# power.net
KiCad netlist of a schematic drawn in Altium Designer
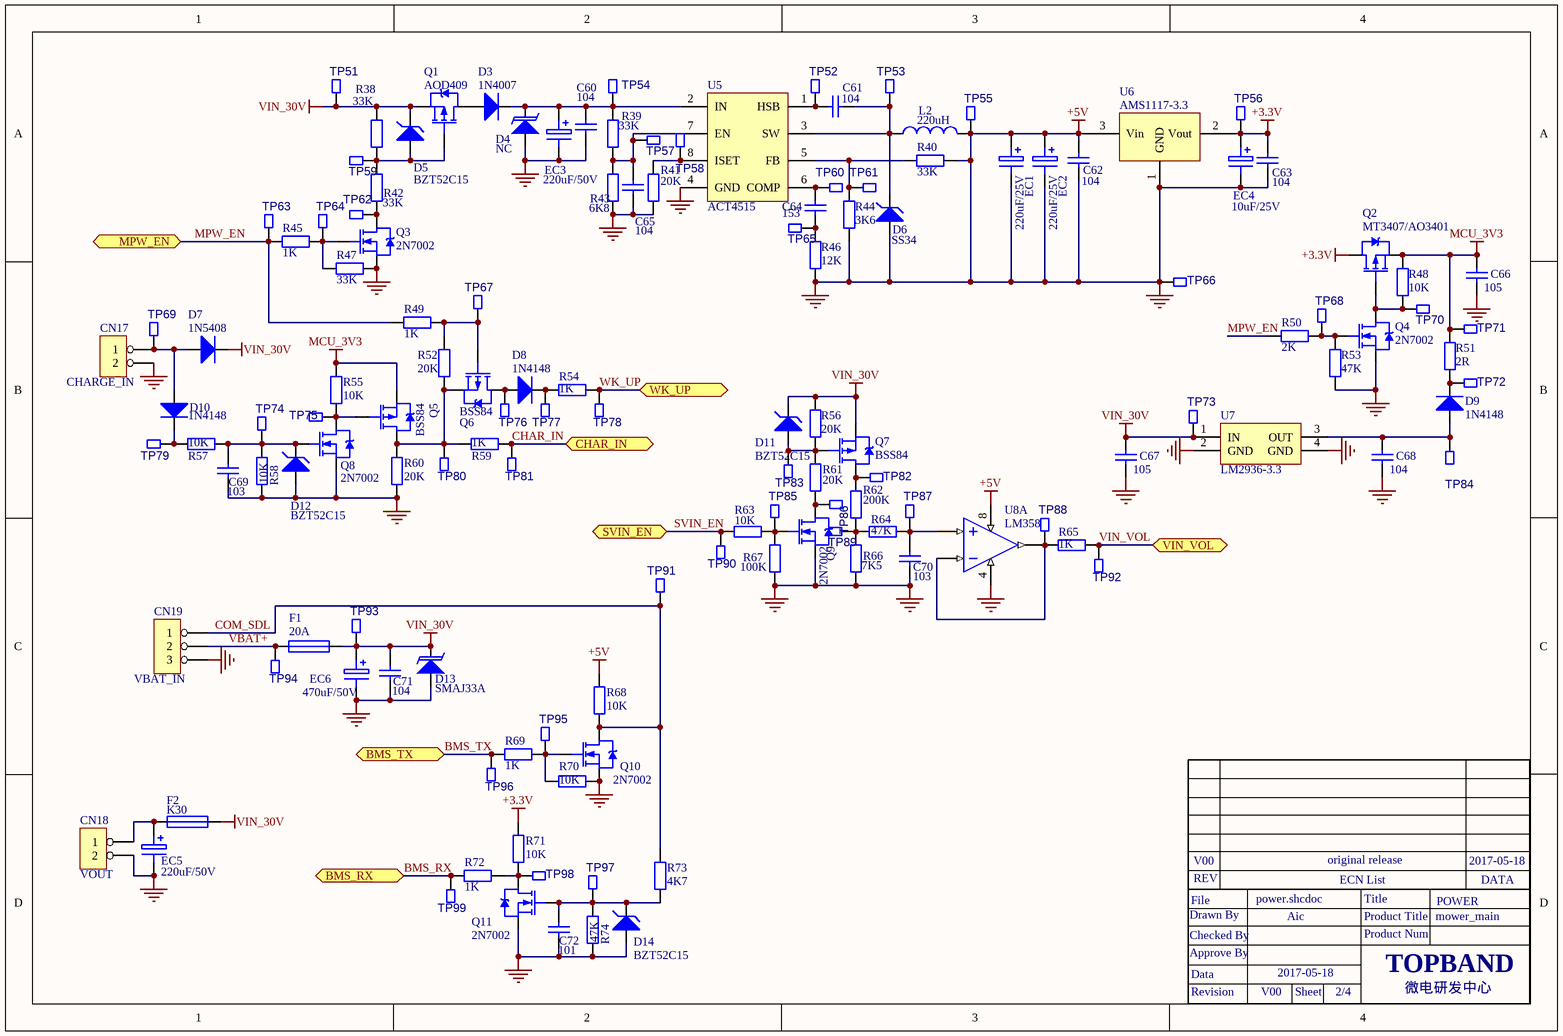
[diagram p0: power.SchDoc]

(export (version "E")
  (design (tool "Eeschema 10.0.6"))
  (components
    (comp (ref "C60")
      (value "104")
      (footprint "0603C")
      (libsource (lib "altium-import") (part "root_1_mirrored_Cap(0603)_"))
    )
    (comp (ref "C61")
      (value "104")
      (footprint "0603C")
      (libsource (lib "altium-import") (part "root_2_mirrored_Cap(0603)_"))
    )
    (comp (ref "C62")
      (value "104")
      (footprint "0603C")
      (libsource (lib "altium-import") (part "root_1_mirrored_Cap(0603)_"))
    )
    (comp (ref "C63")
      (value "104")
      (footprint "0603C")
      (libsource (lib "altium-import") (part "root_1_mirrored_Cap(0603)_"))
    )
    (comp (ref "C64")
      (value "153")
      (footprint "0603C")
      (libsource (lib "altium-import") (part "root_1_mirrored_Cap(0603)_"))
    )
    (comp (ref "C65")
      (value "104")
      (footprint "0603C")
      (libsource (lib "altium-import") (part "root_1_mirrored_Cap(0603)_"))
    )
    (comp (ref "C66")
      (value "105")
      (footprint "0603C")
      (libsource (lib "altium-import") (part "root_1_mirrored_Cap(0603)_"))
    )
    (comp (ref "C67")
      (value "105")
      (footprint "0603C")
      (libsource (lib "altium-import") (part "root_1_mirrored_Cap(0603)_"))
    )
    (comp (ref "C68")
      (value "104")
      (footprint "0603C")
      (libsource (lib "altium-import") (part "root_1_mirrored_Cap(0603)_"))
    )
    (comp (ref "C69")
      (value "103")
      (footprint "0603C")
      (libsource (lib "altium-import") (part "root_3_mirrored_Cap(0603)_"))
    )
    (comp (ref "C70")
      (value "103")
      (footprint "0603C")
      (description "电容器")
      (fields (field (name "PART NUMBER") "Cap(0603)"))
      (libsource (lib "分立器件1") (part "Cap(0603)"))
    )
    (comp (ref "C71")
      (value "104")
      (footprint "0805C")
      (libsource (lib "altium-import") (part "root_3_mirrored_Cap(0603)_"))
    )
    (comp (ref "C72")
      (value "101")
      (footprint "0603C")
      (libsource (lib "altium-import") (part "root_3_mirrored_Cap(0603)_"))
    )
    (comp (ref "CN17")
      (value "CHARGE_IN")
      (footprint "CON2-2.54")
      (description "插座")
      (fields (field (name "PART NUMBER") "2Pin(卧式)"))
      (libsource (lib "接插器件+IC") (part "2Pin(卧式)"))
    )
    (comp (ref "CN18")
      (value "VOUT")
      (footprint "CON2-3.96")
      (description "插座")
      (fields (field (name "PART NUMBER") "2Pin(卧式)"))
      (libsource (lib "接插器件+IC") (part "2Pin(卧式)"))
    )
    (comp (ref "CN19")
      (value "VBAT_IN")
      (footprint "CON3-3.96")
      (description "插座")
      (fields (field (name "PART NUMBER") "3Pin(2~3.96mm)"))
      (libsource (lib "接插器件+IC") (part "3Pin(2~3.96mm)"))
    )
    (comp (ref "D3")
      (value "1N4007")
      (footprint "SMA")
      (description "二极管")
      (fields (field (name "PART NUMBER") "Diode(DO-35)-D"))
      (libsource (lib "分立器件1") (part "Diode(DO-35)-D"))
    )
    (comp (ref "D4")
      (value "NC")
      (footprint "SOD-123")
      (description "TVS管")
      (fields (field (name "PART NUMBER") "Diode(TVS_贴片)_1"))
      (libsource (lib "分立器件1") (part "Diode(TVS_贴片)_1"))
    )
    (comp (ref "D5")
      (value "BZT52C15")
      (footprint "SOD-123")
      (description "稳压二极管")
      (fields (field (name "PART NUMBER") "D Zener(贴片)"))
      (libsource (lib "分立器件1") (part "D Zener(贴片)"))
    )
    (comp (ref "D6")
      (value "SS34")
      (footprint "SMA")
      (description "稳压二极管")
      (fields (field (name "PART NUMBER") "D Zener(贴片)"))
      (libsource (lib "分立器件1") (part "D Zener(贴片)"))
    )
    (comp (ref "D7")
      (value "1N5408")
      (footprint "DIODE")
      (description "二极管")
      (fields (field (name "PART NUMBER") "Diode(DO-35)-D"))
      (libsource (lib "分立器件1") (part "Diode(DO-35)-D"))
    )
    (comp (ref "D8")
      (value "1N4148")
      (footprint "SOD-123")
      (description "二极管")
      (fields (field (name "PART NUMBER") "Diode(DO-35)-D"))
      (libsource (lib "分立器件1") (part "Diode(DO-35)-D"))
    )
    (comp (ref "D9")
      (value "1N4148")
      (footprint "SOD-123")
      (description "二极管")
      (fields (field (name "PART NUMBER") "Diode(DO-35)-D"))
      (libsource (lib "分立器件1") (part "Diode(DO-35)-D"))
    )
    (comp (ref "D10")
      (value "1N4148")
      (footprint "SOD-123")
      (description "二极管")
      (fields (field (name "PART NUMBER") "Diode(DO-35)-D"))
      (libsource (lib "分立器件1") (part "Diode(DO-35)-D"))
    )
    (comp (ref "D11")
      (value "BZT52C15")
      (footprint "SOD-123")
      (description "稳压二极管")
      (fields (field (name "PART NUMBER") "D Zener(贴片)"))
      (libsource (lib "分立器件1") (part "D Zener(贴片)"))
    )
    (comp (ref "D12")
      (value "BZT52C15")
      (footprint "SOD-123")
      (description "稳压二极管")
      (fields (field (name "PART NUMBER") "D Zener(贴片)"))
      (libsource (lib "分立器件1") (part "D Zener(贴片)"))
    )
    (comp (ref "D13")
      (value "SMAJ33A")
      (footprint "DO-214AC")
      (description "TVS管")
      (fields (field (name "PART NUMBER") "Diode(TVS_贴片)_1"))
      (libsource (lib "分立器件1") (part "Diode(TVS_贴片)_1"))
    )
    (comp (ref "D14")
      (value "BZT52C15")
      (footprint "SOD-123")
      (description "稳压二极管")
      (fields (field (name "PART NUMBER") "D Zener(贴片)"))
      (libsource (lib "分立器件1") (part "D Zener(贴片)"))
    )
    (comp (ref "EC1")
      (value "220uF/25V")
      (footprint "EC10")
      (description "电解电容")
      (fields (field (name "PART NUMBER") "Electro(2.5mm)"))
      (libsource (lib "分立器件1") (part "Electro(2.5mm)"))
    )
    (comp (ref "EC2")
      (value "220uF/25V")
      (footprint "EC10")
      (description "电解电容")
      (fields (field (name "PART NUMBER") "Electro(2.5mm)"))
      (libsource (lib "分立器件1") (part "Electro(2.5mm)"))
    )
    (comp (ref "EC3")
      (value "220uF/50V")
      (footprint "EC10")
      (description "电解电容")
      (fields (field (name "PART NUMBER") "Electro(2.5mm)"))
      (libsource (lib "分立器件1") (part "Electro(2.5mm)"))
    )
    (comp (ref "EC4")
      (value "10uF/25V")
      (footprint "EC4")
      (description "电解电容")
      (fields (field (name "PART NUMBER") "Electro(2.5mm)"))
      (libsource (lib "分立器件1") (part "Electro(2.5mm)"))
    )
    (comp (ref "EC5")
      (value "220uF/50V")
      (footprint "EC10")
      (description "电解电容")
      (fields (field (name "PART NUMBER") "Electro(2.5mm)"))
      (libsource (lib "分立器件1") (part "Electro(2.5mm)"))
    )
    (comp (ref "EC6")
      (value "470uF/50V")
      (footprint "EC12.5")
      (description "电解电容")
      (fields (field (name "PART NUMBER") "Electro(2.5mm)"))
      (libsource (lib "分立器件1") (part "Electro(2.5mm)"))
    )
    (comp (ref "F1")
      (value "20A")
      (description "保险管")
      (fields (field (name "PART NUMBER") "Fuse(1206)"))
      (libsource (lib "分立器件1") (part "Fuse(1206)"))
    )
    (comp (ref "F2")
      (value "K30")
      (description "保险管")
      (fields (field (name "PART NUMBER") "Fuse(1206)"))
      (libsource (lib "分立器件1") (part "Fuse(1206)"))
    )
    (comp (ref "L2")
      (value "220uH")
      (footprint "150700618")
      (description "电感")
      (fields (field (name "PART NUMBER") "Inductor(0805)"))
      (libsource (lib "分立器件1") (part "Inductor(0805)"))
    )
    (comp (ref "Q1")
      (value "AOD409")
      (footprint "D-PACK-GDS")
      (description "MOS管")
      (fields (field (name "PART NUMBER") "PMOS-2"))
      (libsource (lib "分立器件1") (part "PMOS-2"))
    )
    (comp (ref "Q2")
      (value "MT3407/AO3401")
      (footprint "SOT23-GDS")
      (description "MOS管")
      (fields (field (name "PART NUMBER") "PMOS-2"))
      (libsource (lib "") (part "PMOS-2_1"))
    )
    (comp (ref "Q3")
      (value "2N7002")
      (footprint "SOT23-GDS")
      (description "MOS管")
      (fields (field (name "PART NUMBER") "NMOS-2"))
      (libsource (lib "分立器件1") (part "NMOS-2"))
    )
    (comp (ref "Q4")
      (value "2N7002")
      (footprint "SOD23-GDS")
      (description "MOS管")
      (fields (field (name "PART NUMBER") "NMOS-2"))
      (libsource (lib "分立器件1") (part "NMOS-2"))
    )
    (comp (ref "Q5")
      (value "BSS84")
      (footprint "SOT-23-GDS")
      (description "MOS管")
      (fields (field (name "PART NUMBER") "PMOS-2"))
      (libsource (lib "") (part "PMOS-2_1"))
    )
    (comp (ref "Q6")
      (value "BSS84")
      (footprint "SOT-23-GDS")
      (description "MOS管")
      (fields (field (name "PART NUMBER") "PMOS-2"))
      (libsource (lib "分立器件1") (part "PMOS-2"))
    )
    (comp (ref "Q7")
      (value "BSS84")
      (footprint "SOT-23-GDS")
      (description "MOS管")
      (fields (field (name "PART NUMBER") "PMOS-2"))
      (libsource (lib "") (part "PMOS-2_1"))
    )
    (comp (ref "Q8")
      (value "2N7002")
      (footprint "SOT-23-GDS")
      (description "MOS管")
      (fields (field (name "PART NUMBER") "NMOS-2"))
      (libsource (lib "分立器件1") (part "NMOS-2"))
    )
    (comp (ref "Q9")
      (value "2N7002")
      (footprint "SOT-23-GDS")
      (description "MOS管")
      (fields (field (name "PART NUMBER") "NMOS-2"))
      (libsource (lib "分立器件1") (part "NMOS-2"))
    )
    (comp (ref "Q10")
      (value "2N7002")
      (footprint "SOT-23-GDS")
      (description "MOS管")
      (fields (field (name "PART NUMBER") "NMOS-2"))
      (libsource (lib "分立器件1") (part "NMOS-2"))
    )
    (comp (ref "Q11")
      (value "2N7002")
      (footprint "SOT-23-GDS")
      (description "MOS管")
      (fields (field (name "PART NUMBER") "NMOS-2"))
      (libsource (lib "分立器件1") (part "NMOS-2"))
    )
    (comp (ref "R38")
      (value "33K")
      (footprint "0603R")
      (description "Resistor")
      (fields (field (name "PUBLISHER") "Altium Limited"))
      (libsource (lib "") (part "Res2_1"))
    )
    (comp (ref "R39")
      (value "33K")
      (footprint "0603R")
      (description "Resistor")
      (fields (field (name "PUBLISHER") "Altium Limited"))
      (libsource (lib "Miscellaneous Devices") (part "Res2"))
    )
    (comp (ref "R40")
      (value "33K")
      (footprint "0603R")
      (description "Resistor")
      (fields (field (name "PUBLISHER") "Altium Limited"))
      (libsource (lib "") (part "Res2_2"))
    )
    (comp (ref "R41")
      (value "20K")
      (footprint "0603R")
      (description "Resistor")
      (fields (field (name "PUBLISHER") "Altium Limited"))
      (libsource (lib "Miscellaneous Devices") (part "Res2"))
    )
    (comp (ref "R42")
      (value "33K")
      (footprint "0603R")
      (description "Resistor")
      (fields (field (name "PUBLISHER") "Altium Limited"))
      (libsource (lib "Miscellaneous Devices") (part "Res2"))
    )
    (comp (ref "R43")
      (value "6K8")
      (footprint "0603R")
      (description "Resistor")
      (fields (field (name "PUBLISHER") "Altium Limited"))
      (libsource (lib "Miscellaneous Devices") (part "Res2"))
    )
    (comp (ref "R44")
      (value "3K6")
      (footprint "0603R")
      (description "Resistor")
      (fields (field (name "PUBLISHER") "Altium Limited"))
      (libsource (lib "") (part "Res2_1"))
    )
    (comp (ref "R45")
      (value "1K")
      (footprint "0603R")
      (description "Resistor")
      (fields (field (name "PUBLISHER") "Altium Limited"))
      (libsource (lib "") (part "Res2_3"))
    )
    (comp (ref "R46")
      (value "12K")
      (footprint "0603R")
      (description "Resistor")
      (fields (field (name "PUBLISHER") "Altium Limited"))
      (libsource (lib "") (part "Res2_1"))
    )
    (comp (ref "R47")
      (value "33K")
      (footprint "0603R")
      (description "Resistor")
      (fields (field (name "PUBLISHER") "Altium Limited"))
      (libsource (lib "") (part "Res2_3"))
    )
    (comp (ref "R48")
      (value "10K")
      (footprint "0603R")
      (description "Resistor")
      (fields (field (name "PUBLISHER") "Altium Limited"))
      (libsource (lib "") (part "Res2_1"))
    )
    (comp (ref "R49")
      (value "1K")
      (footprint "0603R")
      (description "电阻器")
      (fields (field (name "PART NUMBER") "Res(0603)"))
      (libsource (lib "") (part "Res(0603)_1"))
    )
    (comp (ref "R50")
      (value "2K")
      (footprint "0603R")
      (description "Resistor")
      (fields (field (name "PUBLISHER") "Altium Limited"))
      (libsource (lib "") (part "Res2_2"))
    )
    (comp (ref "R51")
      (value "2R")
      (footprint "1206R")
      (description "Resistor")
      (fields (field (name "PUBLISHER") "Altium Limited"))
      (libsource (lib "") (part "Res2_1"))
    )
    (comp (ref "R52")
      (value "20K")
      (footprint "0603R")
      (description "电阻器")
      (fields (field (name "PART NUMBER") "Res(0603)"))
      (libsource (lib "") (part "Res(0603)_3"))
    )
    (comp (ref "R53")
      (value "47K")
      (footprint "0603R")
      (description "Resistor")
      (fields (field (name "PUBLISHER") "Altium Limited"))
      (libsource (lib "") (part "Res2_1"))
    )
    (comp (ref "R54")
      (value "1K")
      (footprint "0603R")
      (description "电阻器")
      (fields (field (name "PART NUMBER") "Res(0603)"))
      (libsource (lib "") (part "Res(0603)_1"))
    )
    (comp (ref "R55")
      (value "10K")
      (footprint "0603R")
      (description "电阻器")
      (fields (field (name "PART NUMBER") "Res(0603)"))
      (libsource (lib "分立器件1") (part "Res(0603)"))
    )
    (comp (ref "R56")
      (value "20K")
      (footprint "0603R")
      (description "电阻器")
      (fields (field (name "PART NUMBER") "Res(1206)"))
      (libsource (lib "分立器件1") (part "Res(1206)"))
    )
    (comp (ref "R57")
      (value "10K")
      (footprint "0603R")
      (description "电阻器")
      (fields (field (name "PART NUMBER") "Res(0603)"))
      (libsource (lib "") (part "Res(0603)_2"))
    )
    (comp (ref "R58")
      (value "10K")
      (footprint "0603R")
      (description "电阻器")
      (fields (field (name "PART NUMBER") "Res(0603)"))
      (libsource (lib "分立器件1") (part "Res(0603)"))
    )
    (comp (ref "R59")
      (value "1K")
      (footprint "0603R")
      (description "电阻器")
      (fields (field (name "PART NUMBER") "Res(0603)"))
      (libsource (lib "") (part "Res(0603)_1"))
    )
    (comp (ref "R60")
      (value "20K")
      (footprint "0603R")
      (description "电阻器")
      (fields (field (name "PART NUMBER") "Res(0603)"))
      (libsource (lib "分立器件1") (part "Res(0603)"))
    )
    (comp (ref "R61")
      (value "20K")
      (footprint "0603R")
      (description "电阻器")
      (fields (field (name "PART NUMBER") "Res(0603)"))
      (libsource (lib "") (part "Res(0603)_3"))
    )
    (comp (ref "R62")
      (value "200K")
      (footprint "0603R")
      (description "电阻器")
      (fields (field (name "PART NUMBER") "Res(0603)"))
      (libsource (lib "分立器件1") (part "Res(0603)"))
    )
    (comp (ref "R63")
      (value "10K")
      (footprint "0603R")
      (description "电阻器")
      (fields (field (name "PART NUMBER") "Res(0603)"))
      (libsource (lib "") (part "Res(0603)_2"))
    )
    (comp (ref "R64")
      (value "47K")
      (footprint "0603R")
      (description "电阻器")
      (fields (field (name "PART NUMBER") "Res(0603)"))
      (libsource (lib "") (part "Res(0603)_2"))
    )
    (comp (ref "R65")
      (value "1K")
      (footprint "0603R")
      (description "电阻器")
      (fields (field (name "PART NUMBER") "Res(0603)"))
      (libsource (lib "") (part "Res(0603)_1"))
    )
    (comp (ref "R66")
      (value "7K5")
      (footprint "0603R")
      (description "电阻器")
      (fields (field (name "PART NUMBER") "Res(0603)"))
      (libsource (lib "分立器件1") (part "Res(0603)"))
    )
    (comp (ref "R67")
      (value "100K")
      (footprint "0603R")
      (description "电阻器")
      (fields (field (name "PART NUMBER") "Res(0603)"))
      (libsource (lib "分立器件1") (part "Res(0603)"))
    )
    (comp (ref "R68")
      (value "10K")
      (footprint "0603R")
      (description "电阻器")
      (fields (field (name "PART NUMBER") "Res(0603)"))
      (libsource (lib "分立器件1") (part "Res(0603)"))
    )
    (comp (ref "R69")
      (value "1K")
      (footprint "0603R")
      (description "电阻器")
      (fields (field (name "PART NUMBER") "Res(0603)"))
      (libsource (lib "") (part "Res(0603)_1"))
    )
    (comp (ref "R70")
      (value "10K")
      (footprint "0603R")
      (description "电阻器")
      (fields (field (name "PART NUMBER") "Res(0603)"))
      (libsource (lib "") (part "Res(0603)_2"))
    )
    (comp (ref "R71")
      (value "10K")
      (footprint "0603R")
      (description "电阻器")
      (fields (field (name "PART NUMBER") "Res(0603)"))
      (libsource (lib "分立器件1") (part "Res(0603)"))
    )
    (comp (ref "R72")
      (value "1K")
      (footprint "0603R")
      (description "电阻器")
      (fields (field (name "PART NUMBER") "Res(0603)"))
      (libsource (lib "") (part "Res(0603)_1"))
    )
    (comp (ref "R73")
      (value "4K7")
      (footprint "0603R")
      (description "电阻器")
      (fields (field (name "PART NUMBER") "Res(0603)"))
      (libsource (lib "分立器件1") (part "Res(0603)"))
    )
    (comp (ref "R74")
      (value "47K")
      (footprint "0603R")
      (description "电阻器")
      (fields (field (name "PART NUMBER") "Res(0603)"))
      (libsource (lib "分立器件1") (part "Res(0603)"))
    )
    (comp (ref "TP51") (value "TP") (footprint "TEST-0.8MM") (libsource (lib "Topband1") (part "TP")))
    (comp (ref "TP52") (value "TP") (footprint "TEST-0.8MM") (libsource (lib "Topband1") (part "TP")))
    (comp (ref "TP53") (value "TP") (footprint "TEST-0.8MM") (libsource (lib "Topband1") (part "TP")))
    (comp (ref "TP54") (value "TP") (footprint "TEST-0.8MM") (libsource (lib "Topband1") (part "TP")))
    (comp (ref "TP55") (value "TP") (footprint "TEST-0.8MM") (libsource (lib "Topband1") (part "TP")))
    (comp (ref "TP56") (value "TP") (footprint "TEST-0.8MM") (libsource (lib "Topband1") (part "TP")))
    (comp (ref "TP57") (value "TP") (footprint "TEST-0.8MM") (libsource (lib "Topband1") (part "TP")))
    (comp (ref "TP58") (value "TP") (footprint "TEST-0.8MM") (libsource (lib "Topband1") (part "TP")))
    (comp (ref "TP59") (value "TP") (footprint "TEST-0.8MM") (libsource (lib "Topband1") (part "TP")))
    (comp (ref "TP60") (value "TP") (footprint "TEST-0.8MM") (libsource (lib "Topband1") (part "TP")))
    (comp (ref "TP61") (value "TP") (footprint "TEST-0.8MM") (libsource (lib "Topband1") (part "TP")))
    (comp (ref "TP62") (value "TP") (footprint "TEST-0.8MM") (libsource (lib "Topband1") (part "TP")))
    (comp (ref "TP63") (value "TP") (footprint "TEST-0.8MM") (libsource (lib "Topband1") (part "TP")))
    (comp (ref "TP64") (value "TP") (footprint "TEST-0.8MM") (libsource (lib "Topband1") (part "TP")))
    (comp (ref "TP65") (value "TP") (footprint "TEST-0.8MM") (libsource (lib "Topband1") (part "TP")))
    (comp (ref "TP66") (value "TP") (footprint "TEST-0.8MM") (libsource (lib "Topband1") (part "TP")))
    (comp (ref "TP67") (value "TP") (footprint "TEST-0.8MM") (libsource (lib "Topband1") (part "TP")))
    (comp (ref "TP68") (value "TP") (footprint "TEST-0.8MM") (libsource (lib "Topband1") (part "TP")))
    (comp (ref "TP69") (value "TP") (footprint "TEST-0.8MM") (libsource (lib "Topband1") (part "TP")))
    (comp (ref "TP70") (value "TP") (footprint "TEST-0.8MM") (libsource (lib "Topband1") (part "TP")))
    (comp (ref "TP71") (value "TP") (footprint "TEST-0.8MM") (libsource (lib "Topband1") (part "TP")))
    (comp (ref "TP72") (value "TP") (footprint "TEST-0.8MM") (libsource (lib "Topband1") (part "TP")))
    (comp (ref "TP73") (value "TP") (footprint "TEST-0.8MM") (libsource (lib "Topband1") (part "TP")))
    (comp (ref "TP74") (value "TP") (footprint "TEST-0.8MM") (libsource (lib "Topband1") (part "TP")))
    (comp (ref "TP75") (value "TP") (footprint "TEST-0.8MM") (libsource (lib "Topband1") (part "TP")))
    (comp (ref "TP76") (value "TP") (footprint "TEST-0.8MM") (libsource (lib "Topband1") (part "TP")))
    (comp (ref "TP77") (value "TP") (footprint "TEST-0.8MM") (libsource (lib "Topband1") (part "TP")))
    (comp (ref "TP78") (value "TP") (footprint "TEST-0.8MM") (libsource (lib "Topband1") (part "TP")))
    (comp (ref "TP79") (value "TP") (footprint "TEST-0.8MM") (libsource (lib "Topband1") (part "TP")))
    (comp (ref "TP80") (value "TP") (footprint "TEST-0.8MM") (libsource (lib "Topband1") (part "TP")))
    (comp (ref "TP81") (value "TP") (footprint "TEST-0.8MM") (libsource (lib "Topband1") (part "TP")))
    (comp (ref "TP82") (value "TP") (footprint "TEST-0.8MM") (libsource (lib "Topband1") (part "TP")))
    (comp (ref "TP83") (value "TP") (footprint "TEST-0.8MM") (libsource (lib "Topband1") (part "TP")))
    (comp (ref "TP84") (value "TP") (footprint "TEST-0.8MM") (libsource (lib "Topband1") (part "TP")))
    (comp (ref "TP85") (value "TP") (footprint "TEST-0.8MM") (libsource (lib "Topband1") (part "TP")))
    (comp (ref "TP86") (value "TP") (footprint "TEST-0.8MM") (libsource (lib "Topband1") (part "TP")))
    (comp (ref "TP87") (value "TP") (footprint "TEST-0.8MM") (libsource (lib "Topband1") (part "TP")))
    (comp (ref "TP88") (value "TP") (footprint "TEST-0.8MM") (libsource (lib "Topband1") (part "TP")))
    (comp (ref "TP89") (value "TP") (footprint "TEST-0.8MM") (libsource (lib "Topband1") (part "TP")))
    (comp (ref "TP90") (value "TP") (footprint "TEST-0.8MM") (libsource (lib "Topband1") (part "TP")))
    (comp (ref "TP91") (value "TP") (footprint "TEST-0.8MM") (libsource (lib "Topband1") (part "TP")))
    (comp (ref "TP92") (value "TP") (footprint "TEST-0.8MM") (libsource (lib "Topband1") (part "TP")))
    (comp (ref "TP93") (value "TP") (footprint "TEST-0.8MM") (libsource (lib "Topband1") (part "TP")))
    (comp (ref "TP94") (value "TP") (footprint "TEST-0.8MM") (libsource (lib "Topband1") (part "TP")))
    (comp (ref "TP95") (value "TP") (footprint "TEST-0.8MM") (libsource (lib "Topband1") (part "TP")))
    (comp (ref "TP96") (value "TP") (footprint "TEST-0.8MM") (libsource (lib "Topband1") (part "TP")))
    (comp (ref "TP97") (value "TP") (footprint "TEST-0.8MM") (libsource (lib "Topband1") (part "TP")))
    (comp (ref "TP98") (value "TP") (footprint "TEST-0.8MM") (libsource (lib "Topband1") (part "TP")))
    (comp (ref "TP99") (value "TP") (footprint "TEST-0.8MM") (libsource (lib "Topband1") (part "TP")))
    (comp (ref "U5") (value "ACT4515") (footprint "SOP-8") (libsource (lib "Schlib1") (part "ACT4515")))
    (comp (ref "U6") (value "AMS1117-3.3") (footprint "SOT-223") (libsource (lib "IC") (part "AMS1117-3.3")))
    (comp (ref "U7") (value "LM2936-3.3") (footprint "SOT-223") (libsource (lib "Schlib1") (part "LM2936")))
    (comp (ref "U8")
      (value "LM358")
      (footprint "SO-8")
      (description "集成电路")
      (fields (field (name "PART NUMBER") "IC_LM358"))
      (libsource (lib "接插器件+IC") (part "IC_LM358"))
    )
  )
  (nets
    (net (code "1") (name "+3.3V") (class "Default")
      (node (ref "C63") (pin "1") (pinfunction "1_1") (pintype "passive"))
      (node (ref "EC4") (pin "1") (pinfunction "1_1") (pintype "passive"))
      (node (ref "Q2") (pin "D") (pinfunction "D_D") (pintype "passive"))
      (node (ref "R71") (pin "1") (pinfunction "1_1") (pintype "passive"))
      (node (ref "TP56") (pin "1") (pintype "passive"))
      (node (ref "U6") (pin "2") (pinfunction "Vout_2") (pintype "passive"))
    )
    (net (code "2") (name "+5V") (class "Default")
      (node (ref "C60") (pin "2") (pinfunction "2_2") (pintype "passive"))
      (node (ref "C62") (pin "1") (pinfunction "1_1") (pintype "passive"))
      (node (ref "C62") (pin "2") (pinfunction "2_2") (pintype "passive"))
      (node (ref "C63") (pin "2") (pinfunction "2_2") (pintype "passive"))
      (node (ref "C65") (pin "2") (pinfunction "2_2") (pintype "passive"))
      (node (ref "C66") (pin "2") (pinfunction "2_2") (pintype "passive"))
      (node (ref "C67") (pin "2") (pinfunction "2_2") (pintype "passive"))
      (node (ref "C68") (pin "2") (pinfunction "2_2") (pintype "passive"))
      (node (ref "C69") (pin "1") (pinfunction "1_1") (pintype "passive"))
      (node (ref "C70") (pin "2") (pinfunction "2_2") (pintype "passive"))
      (node (ref "C71") (pin "1") (pinfunction "1_1") (pintype "passive"))
      (node (ref "C72") (pin "1") (pinfunction "1_1") (pintype "passive"))
      (node (ref "CN17") (pin "2") (pinfunction "2_2") (pintype "passive"))
      (node (ref "CN18") (pin "2") (pinfunction "2_2") (pintype "passive"))
      (node (ref "CN19") (pin "3") (pinfunction "3_3") (pintype "passive"))
      (node (ref "D12") (pin "A") (pinfunction "A_A") (pintype "passive"))
      (node (ref "D13") (pin "A") (pinfunction "A_A") (pintype "passive"))
      (node (ref "D14") (pin "A") (pinfunction "A_A") (pintype "passive"))
      (node (ref "D4") (pin "A") (pinfunction "A_A") (pintype "passive"))
      (node (ref "D6") (pin "A") (pinfunction "A_A") (pintype "passive"))
      (node (ref "EC1") (pin "1") (pinfunction "1_1") (pintype "passive"))
      (node (ref "EC1") (pin "2") (pinfunction "2_2") (pintype "passive"))
      (node (ref "EC2") (pin "1") (pinfunction "1_1") (pintype "passive"))
      (node (ref "EC2") (pin "2") (pinfunction "2_2") (pintype "passive"))
      (node (ref "EC3") (pin "2") (pinfunction "2_2") (pintype "passive"))
      (node (ref "EC4") (pin "2") (pinfunction "2_2") (pintype "passive"))
      (node (ref "EC5") (pin "2") (pinfunction "2_2") (pintype "passive"))
      (node (ref "EC6") (pin "2") (pinfunction "2_2") (pintype "passive"))
      (node (ref "L2") (pin "2") (pinfunction "2_2") (pintype "passive"))
      (node (ref "Q10") (pin "S") (pinfunction "S_S") (pintype "passive"))
      (node (ref "Q11") (pin "S") (pinfunction "S_S") (pintype "passive"))
      (node (ref "Q3") (pin "S") (pinfunction "S_S") (pintype "passive"))
      (node (ref "Q4") (pin "S") (pinfunction "S_S") (pintype "passive"))
      (node (ref "Q8") (pin "S") (pinfunction "S_S") (pintype "passive"))
      (node (ref "Q9") (pin "S") (pinfunction "S_S") (pintype "passive"))
      (node (ref "R40") (pin "1") (pinfunction "1_1") (pintype "passive"))
      (node (ref "R41") (pin "2") (pinfunction "2_2") (pintype "passive"))
      (node (ref "R43") (pin "2") (pinfunction "2_2") (pintype "passive"))
      (node (ref "R44") (pin "1") (pinfunction "1_1") (pintype "passive"))
      (node (ref "R46") (pin "1") (pinfunction "1_1") (pintype "passive"))
      (node (ref "R47") (pin "2") (pinfunction "2_2") (pintype "passive"))
      (node (ref "R53") (pin "1") (pinfunction "1_1") (pintype "passive"))
      (node (ref "R58") (pin "2") (pinfunction "2_2") (pintype "passive"))
      (node (ref "R60") (pin "2") (pinfunction "2_2") (pintype "passive"))
      (node (ref "R66") (pin "2") (pinfunction "2_2") (pintype "passive"))
      (node (ref "R67") (pin "2") (pinfunction "2_2") (pintype "passive"))
      (node (ref "R68") (pin "1") (pinfunction "1_1") (pintype "passive"))
      (node (ref "R70") (pin "1") (pinfunction "1_1") (pintype "passive"))
      (node (ref "R74") (pin "2") (pinfunction "2_2") (pintype "passive"))
      (node (ref "TP55") (pin "1") (pintype "passive"))
      (node (ref "TP66") (pin "1") (pintype "passive"))
      (node (ref "U5") (pin "4") (pinfunction "GND_4") (pintype "passive"))
      (node (ref "U6") (pin "1") (pinfunction "GND_1") (pintype "passive"))
      (node (ref "U6") (pin "3") (pinfunction "Vin_3") (pintype "passive"))
      (node (ref "U7") (pin "2") (pinfunction "GND_2") (pintype "passive"))
      (node (ref "U7") (pin "4") (pinfunction "GND_4") (pintype "passive"))
      (node (ref "U8") (pin "4") (pinfunction "GND_4") (pintype "input"))
      (node (ref "U8") (pin "8") (pinfunction "VCC_8") (pintype "input"))
    )
    (net (code "3") (name "/BMS_RX") (class "Default")
      (node (ref "R72") (pin "1") (pinfunction "1_1") (pintype "passive"))
      (node (ref "TP99") (pin "1") (pintype "passive"))
    )
    (net (code "4") (name "/BMS_TX") (class "Default")
      (node (ref "R69") (pin "1") (pinfunction "1_1") (pintype "passive"))
      (node (ref "TP96") (pin "1") (pintype "passive"))
    )
    (net (code "5") (name "/CHAR_IN") (class "Default")
      (node (ref "R59") (pin "2") (pinfunction "2_2") (pintype "passive"))
      (node (ref "TP81") (pin "1") (pintype "passive"))
    )
    (net (code "6") (name "/COM_SDL") (class "Default")
      (node (ref "CN19") (pin "1") (pinfunction "1_1") (pintype "passive"))
      (node (ref "Q10") (pin "D") (pinfunction "D_D") (pintype "passive"))
      (node (ref "R68") (pin "2") (pinfunction "2_2") (pintype "passive"))
      (node (ref "R73") (pin "1") (pinfunction "1_1") (pintype "passive"))
      (node (ref "TP91") (pin "1") (pintype "passive"))
    )
    (net (code "7") (name "/MPW_EN") (class "Default")
      (node (ref "R45") (pin "1") (pinfunction "1_1") (pintype "passive"))
      (node (ref "R49") (pin "1") (pinfunction "1_1") (pintype "passive"))
      (node (ref "R50") (pin "2") (pinfunction "2_2") (pintype "passive"))
      (node (ref "TP63") (pin "1") (pintype "passive"))
    )
    (net (code "8") (name "/SVIN_EN") (class "Default")
      (node (ref "R63") (pin "2") (pinfunction "2_2") (pintype "passive"))
      (node (ref "TP90") (pin "1") (pintype "passive"))
    )
    (net (code "9") (name "/VBAT+") (class "Default")
      (node (ref "CN19") (pin "2") (pinfunction "2_2") (pintype "passive"))
      (node (ref "F1") (pin "1") (pinfunction "1_1") (pintype "passive"))
      (node (ref "TP94") (pin "1") (pintype "passive"))
    )
    (net (code "10") (name "/VIN_VOL") (class "Default")
      (node (ref "R65") (pin "2") (pinfunction "2_2") (pintype "passive"))
      (node (ref "TP92") (pin "1") (pintype "passive"))
    )
    (net (code "11") (name "/WK_UP") (class "Default")
      (node (ref "R54") (pin "2") (pinfunction "2_2") (pintype "passive"))
      (node (ref "TP78") (pin "1") (pintype "passive"))
    )
    (net (code "12") (name "MCU_3V3") (class "Default")
      (node (ref "C66") (pin "1") (pinfunction "1_1") (pintype "passive"))
      (node (ref "Q2") (pin "S") (pinfunction "S_S") (pintype "passive"))
      (node (ref "Q5") (pin "S") (pinfunction "S_S") (pintype "passive"))
      (node (ref "R48") (pin "2") (pinfunction "2_2") (pintype "passive"))
      (node (ref "R51") (pin "2") (pinfunction "2_2") (pintype "passive"))
      (node (ref "R55") (pin "1") (pinfunction "1_1") (pintype "passive"))
      (node (ref "TP71") (pin "1") (pintype "passive"))
    )
    (net (code "13") (name "Net-(C64-Pad2)") (class "Default")
      (node (ref "C64") (pin "2") (pinfunction "2_2") (pintype "passive"))
      (node (ref "R46") (pin "2") (pinfunction "2_2") (pintype "passive"))
      (node (ref "TP65") (pin "1") (pintype "passive"))
    )
    (net (code "14") (name "Net-(C69-Pad2)") (class "Default")
      (node (ref "C69") (pin "2") (pinfunction "2_2") (pintype "passive"))
      (node (ref "D12") (pin "K") (pinfunction "K_K") (pintype "passive"))
      (node (ref "Q8") (pin "G") (pinfunction "G_G") (pintype "passive"))
      (node (ref "R57") (pin "1") (pinfunction "1_1") (pintype "passive"))
      (node (ref "R58") (pin "1") (pinfunction "1_1") (pintype "passive"))
      (node (ref "TP74") (pin "1") (pintype "passive"))
    )
    (net (code "15") (name "Net-(C72-Pad2)") (class "Default")
      (node (ref "C72") (pin "2") (pinfunction "2_2") (pintype "passive"))
      (node (ref "D14") (pin "K") (pinfunction "K_K") (pintype "passive"))
      (node (ref "Q11") (pin "G") (pinfunction "G_G") (pintype "passive"))
      (node (ref "R73") (pin "2") (pinfunction "2_2") (pintype "passive"))
      (node (ref "R74") (pin "1") (pinfunction "1_1") (pintype "passive"))
      (node (ref "TP97") (pin "1") (pintype "passive"))
    )
    (net (code "16") (name "Net-(CN17-Pad1)") (class "Default")
      (node (ref "CN17") (pin "1") (pinfunction "1_1") (pintype "passive"))
      (node (ref "D10") (pin "A") (pinfunction "A_A") (pintype "passive"))
      (node (ref "D7") (pin "A") (pinfunction "A_A") (pintype "passive"))
      (node (ref "TP69") (pin "1") (pintype "passive"))
    )
    (net (code "17") (name "Net-(CN18-Pad1)") (class "Default")
      (node (ref "CN18") (pin "1") (pinfunction "1_1") (pintype "passive"))
      (node (ref "EC5") (pin "1") (pinfunction "1_1") (pintype "passive"))
      (node (ref "F2") (pin "1") (pinfunction "1_1") (pintype "passive"))
    )
    (net (code "18") (name "Net-(D3-PadA)") (class "Default")
      (node (ref "D3") (pin "A") (pinfunction "A_A") (pintype "passive"))
      (node (ref "Q1") (pin "D") (pinfunction "D_D") (pintype "passive"))
    )
    (net (code "19") (name "Net-(D5-PadA)") (class "Default")
      (node (ref "D5") (pin "A") (pinfunction "A_A") (pintype "passive"))
      (node (ref "Q1") (pin "G") (pinfunction "G_G") (pintype "passive"))
      (node (ref "R38") (pin "1") (pinfunction "1_1") (pintype "passive"))
      (node (ref "R42") (pin "1") (pinfunction "1_1") (pintype "passive"))
      (node (ref "TP59") (pin "1") (pintype "passive"))
    )
    (net (code "20") (name "Net-(D8-PadA)") (class "Default")
      (node (ref "D8") (pin "A") (pinfunction "A_A") (pintype "passive"))
      (node (ref "Q6") (pin "D") (pinfunction "D_D") (pintype "passive"))
      (node (ref "TP76") (pin "1") (pintype "passive"))
    )
    (net (code "21") (name "Net-(D8-PadK)") (class "Default")
      (node (ref "D8") (pin "K") (pinfunction "K_K") (pintype "passive"))
      (node (ref "R54") (pin "1") (pinfunction "1_1") (pintype "passive"))
      (node (ref "TP77") (pin "1") (pintype "passive"))
    )
    (net (code "22") (name "Net-(D9-PadK)") (class "Default")
      (node (ref "D9") (pin "K") (pinfunction "K_K") (pintype "passive"))
      (node (ref "R51") (pin "1") (pinfunction "1_1") (pintype "passive"))
      (node (ref "TP72") (pin "1") (pintype "passive"))
    )
    (net (code "23") (name "Net-(D10-PadK)") (class "Default")
      (node (ref "D10") (pin "K") (pinfunction "K_K") (pintype "passive"))
      (node (ref "R57") (pin "2") (pinfunction "2_2") (pintype "passive"))
      (node (ref "TP79") (pin "1") (pintype "passive"))
    )
    (net (code "24") (name "Net-(D11-PadA)") (class "Default")
      (node (ref "D11") (pin "A") (pinfunction "A_A") (pintype "passive"))
      (node (ref "Q7") (pin "G") (pinfunction "G_G") (pintype "passive"))
      (node (ref "R56") (pin "1") (pinfunction "1_1") (pintype "passive"))
      (node (ref "R61") (pin "2") (pinfunction "2_2") (pintype "passive"))
      (node (ref "TP83") (pin "1") (pintype "passive"))
    )
    (net (code "25") (name "Net-(Q2-PadG)") (class "Default")
      (node (ref "Q2") (pin "G") (pinfunction "G_G") (pintype "passive"))
      (node (ref "Q4") (pin "D") (pinfunction "D_D") (pintype "passive"))
      (node (ref "R48") (pin "1") (pinfunction "1_1") (pintype "passive"))
      (node (ref "TP70") (pin "1") (pintype "passive"))
    )
    (net (code "26") (name "Net-(Q3-PadD)") (class "Default")
      (node (ref "Q3") (pin "D") (pinfunction "D_D") (pintype "passive"))
      (node (ref "R42") (pin "2") (pinfunction "2_2") (pintype "passive"))
      (node (ref "TP62") (pin "1") (pintype "passive"))
    )
    (net (code "27") (name "Net-(Q3-PadG)") (class "Default")
      (node (ref "Q3") (pin "G") (pinfunction "G_G") (pintype "passive"))
      (node (ref "R45") (pin "2") (pinfunction "2_2") (pintype "passive"))
      (node (ref "R47") (pin "1") (pinfunction "1_1") (pintype "passive"))
      (node (ref "TP64") (pin "1") (pintype "passive"))
    )
    (net (code "28") (name "Net-(Q4-PadG)") (class "Default")
      (node (ref "Q4") (pin "G") (pinfunction "G_G") (pintype "passive"))
      (node (ref "R50") (pin "1") (pinfunction "1_1") (pintype "passive"))
      (node (ref "R53") (pin "2") (pinfunction "2_2") (pintype "passive"))
      (node (ref "TP68") (pin "1") (pintype "passive"))
    )
    (net (code "29") (name "Net-(Q5-PadD)") (class "Default")
      (node (ref "Q5") (pin "D") (pinfunction "D_D") (pintype "passive"))
      (node (ref "Q6") (pin "S") (pinfunction "S_S") (pintype "passive"))
      (node (ref "R52") (pin "1") (pinfunction "1_1") (pintype "passive"))
      (node (ref "R59") (pin "1") (pinfunction "1_1") (pintype "passive"))
      (node (ref "R60") (pin "1") (pinfunction "1_1") (pintype "passive"))
      (node (ref "TP80") (pin "1") (pintype "passive"))
    )
    (net (code "30") (name "Net-(Q5-PadG)") (class "Default")
      (node (ref "Q5") (pin "G") (pinfunction "G_G") (pintype "passive"))
      (node (ref "Q8") (pin "D") (pinfunction "D_D") (pintype "passive"))
      (node (ref "R55") (pin "2") (pinfunction "2_2") (pintype "passive"))
      (node (ref "TP75") (pin "1") (pintype "passive"))
    )
    (net (code "31") (name "Net-(Q6-PadG)") (class "Default")
      (node (ref "Q6") (pin "G") (pinfunction "G_G") (pintype "passive"))
      (node (ref "R49") (pin "2") (pinfunction "2_2") (pintype "passive"))
      (node (ref "R52") (pin "2") (pinfunction "2_2") (pintype "passive"))
      (node (ref "TP67") (pin "1") (pintype "passive"))
    )
    (net (code "32") (name "Net-(Q7-PadD)") (class "Default")
      (node (ref "Q7") (pin "D") (pinfunction "D_D") (pintype "passive"))
      (node (ref "R62") (pin "1") (pinfunction "1_1") (pintype "passive"))
      (node (ref "TP82") (pin "1") (pintype "passive"))
    )
    (net (code "33") (name "Net-(Q9-PadD)") (class "Default")
      (node (ref "Q9") (pin "D") (pinfunction "D_D") (pintype "passive"))
      (node (ref "R61") (pin "1") (pinfunction "1_1") (pintype "passive"))
      (node (ref "TP86") (pin "1") (pintype "passive"))
    )
    (net (code "34") (name "Net-(Q9-PadG)") (class "Default")
      (node (ref "Q9") (pin "G") (pinfunction "G_G") (pintype "passive"))
      (node (ref "R63") (pin "1") (pinfunction "1_1") (pintype "passive"))
      (node (ref "R67") (pin "1") (pinfunction "1_1") (pintype "passive"))
      (node (ref "TP85") (pin "1") (pintype "passive"))
    )
    (net (code "35") (name "Net-(Q10-PadG)") (class "Default")
      (node (ref "Q10") (pin "G") (pinfunction "G_G") (pintype "passive"))
      (node (ref "R69") (pin "2") (pinfunction "2_2") (pintype "passive"))
      (node (ref "R70") (pin "2") (pinfunction "2_2") (pintype "passive"))
      (node (ref "TP95") (pin "1") (pintype "passive"))
    )
    (net (code "36") (name "Net-(Q11-PadD)") (class "Default")
      (node (ref "Q11") (pin "D") (pinfunction "D_D") (pintype "passive"))
      (node (ref "R71") (pin "2") (pinfunction "2_2") (pintype "passive"))
      (node (ref "R72") (pin "2") (pinfunction "2_2") (pintype "passive"))
      (node (ref "TP98") (pin "1") (pintype "passive"))
    )
    (net (code "37") (name "Net-(R62-Pad2)") (class "Default")
      (node (ref "R62") (pin "2") (pinfunction "2_2") (pintype "passive"))
      (node (ref "R64") (pin "2") (pinfunction "2_2") (pintype "passive"))
      (node (ref "R66") (pin "1") (pinfunction "1_1") (pintype "passive"))
      (node (ref "TP89") (pin "1") (pintype "passive"))
    )
    (net (code "38") (name "Net-(U5-COMP)") (class "Default")
      (node (ref "C64") (pin "1") (pinfunction "1_1") (pintype "passive"))
      (node (ref "TP60") (pin "1") (pintype "passive"))
      (node (ref "U5") (pin "6") (pinfunction "COMP_6") (pintype "passive"))
    )
    (net (code "39") (name "Net-(U5-EN)") (class "Default")
      (node (ref "C65") (pin "1") (pinfunction "1_1") (pintype "passive"))
      (node (ref "R39") (pin "2") (pinfunction "2_2") (pintype "passive"))
      (node (ref "R43") (pin "1") (pinfunction "1_1") (pintype "passive"))
      (node (ref "TP57") (pin "1") (pintype "passive"))
      (node (ref "U5") (pin "7") (pinfunction "EN_7") (pintype "passive"))
    )
    (net (code "40") (name "Net-(U5-FB)") (class "Default")
      (node (ref "R40") (pin "2") (pinfunction "2_2") (pintype "passive"))
      (node (ref "R44") (pin "2") (pinfunction "2_2") (pintype "passive"))
      (node (ref "TP61") (pin "1") (pintype "passive"))
      (node (ref "U5") (pin "5") (pinfunction "FB_5") (pintype "passive"))
    )
    (net (code "41") (name "Net-(U5-HSB)") (class "Default")
      (node (ref "C61") (pin "1") (pinfunction "1_1") (pintype "passive"))
      (node (ref "TP52") (pin "1") (pintype "passive"))
      (node (ref "U5") (pin "1") (pinfunction "HSB_1") (pintype "passive"))
    )
    (net (code "42") (name "Net-(U5-IN)") (class "Default")
      (node (ref "C60") (pin "1") (pinfunction "1_1") (pintype "passive"))
      (node (ref "D3") (pin "K") (pinfunction "K_K") (pintype "passive"))
      (node (ref "D4") (pin "K") (pinfunction "K_K") (pintype "passive"))
      (node (ref "EC3") (pin "1") (pinfunction "1_1") (pintype "passive"))
      (node (ref "R39") (pin "1") (pinfunction "1_1") (pintype "passive"))
      (node (ref "TP54") (pin "1") (pintype "passive"))
      (node (ref "U5") (pin "2") (pinfunction "IN_2") (pintype "passive"))
    )
    (net (code "43") (name "Net-(U5-ISET)") (class "Default")
      (node (ref "R41") (pin "1") (pinfunction "1_1") (pintype "passive"))
      (node (ref "TP58") (pin "1") (pintype "passive"))
      (node (ref "U5") (pin "8") (pinfunction "ISET_8") (pintype "passive"))
    )
    (net (code "44") (name "Net-(U5-SW)") (class "Default")
      (node (ref "C61") (pin "2") (pinfunction "2_2") (pintype "passive"))
      (node (ref "D6") (pin "K") (pinfunction "K_K") (pintype "passive"))
      (node (ref "L2") (pin "1") (pinfunction "1_1") (pintype "passive"))
      (node (ref "TP53") (pin "1") (pintype "passive"))
      (node (ref "U5") (pin "3") (pinfunction "SW_3") (pintype "passive"))
    )
    (net (code "45") (name "Net-(U7-OUT)") (class "Default")
      (node (ref "C68") (pin "1") (pinfunction "1_1") (pintype "passive"))
      (node (ref "D9") (pin "A") (pinfunction "A_A") (pintype "passive"))
      (node (ref "TP84") (pin "1") (pintype "passive"))
      (node (ref "U7") (pin "3") (pinfunction "OUT_3") (pintype "passive"))
    )
    (net (code "46") (name "Net-(U8A-+IN1)") (class "Default")
      (node (ref "C70") (pin "1") (pinfunction "1_1") (pintype "passive"))
      (node (ref "R64") (pin "1") (pinfunction "1_1") (pintype "passive"))
      (node (ref "TP87") (pin "1") (pintype "passive"))
      (node (ref "U8") (pin "5") (pinfunction "+IN1_5") (pintype "input"))
    )
    (net (code "47") (name "Net-(U8A--IN1)") (class "Default")
      (node (ref "R65") (pin "1") (pinfunction "1_1") (pintype "passive"))
      (node (ref "TP88") (pin "1") (pintype "passive"))
      (node (ref "U8") (pin "6") (pinfunction "-IN1_6") (pintype "input"))
      (node (ref "U8") (pin "7") (pinfunction "OUT1_7") (pintype "output"))
    )
    (net (code "48") (name "VIN_30V") (class "Default")
      (node (ref "C67") (pin "1") (pinfunction "1_1") (pintype "passive"))
      (node (ref "C71") (pin "2") (pinfunction "2_2") (pintype "passive"))
      (node (ref "D11") (pin "K") (pinfunction "K_K") (pintype "passive"))
      (node (ref "D13") (pin "K") (pinfunction "K_K") (pintype "passive"))
      (node (ref "D5") (pin "K") (pinfunction "K_K") (pintype "passive"))
      (node (ref "D7") (pin "K") (pinfunction "K_K") (pintype "passive"))
      (node (ref "EC6") (pin "1") (pinfunction "1_1") (pintype "passive"))
      (node (ref "F1") (pin "2") (pinfunction "2_2") (pintype "passive"))
      (node (ref "F2") (pin "2") (pinfunction "2_2") (pintype "passive"))
      (node (ref "Q1") (pin "S") (pinfunction "S_S") (pintype "passive"))
      (node (ref "Q7") (pin "S") (pinfunction "S_S") (pintype "passive"))
      (node (ref "R38") (pin "2") (pinfunction "2_2") (pintype "passive"))
      (node (ref "R56") (pin "2") (pinfunction "2_2") (pintype "passive"))
      (node (ref "TP51") (pin "1") (pintype "passive"))
      (node (ref "TP73") (pin "1") (pintype "passive"))
      (node (ref "TP93") (pin "1") (pintype "passive"))
      (node (ref "U7") (pin "1") (pinfunction "IN_1") (pintype "passive"))
    )
  )
)
